# TOP.net
KiCad netlist of a schematic drawn in Altium Designer
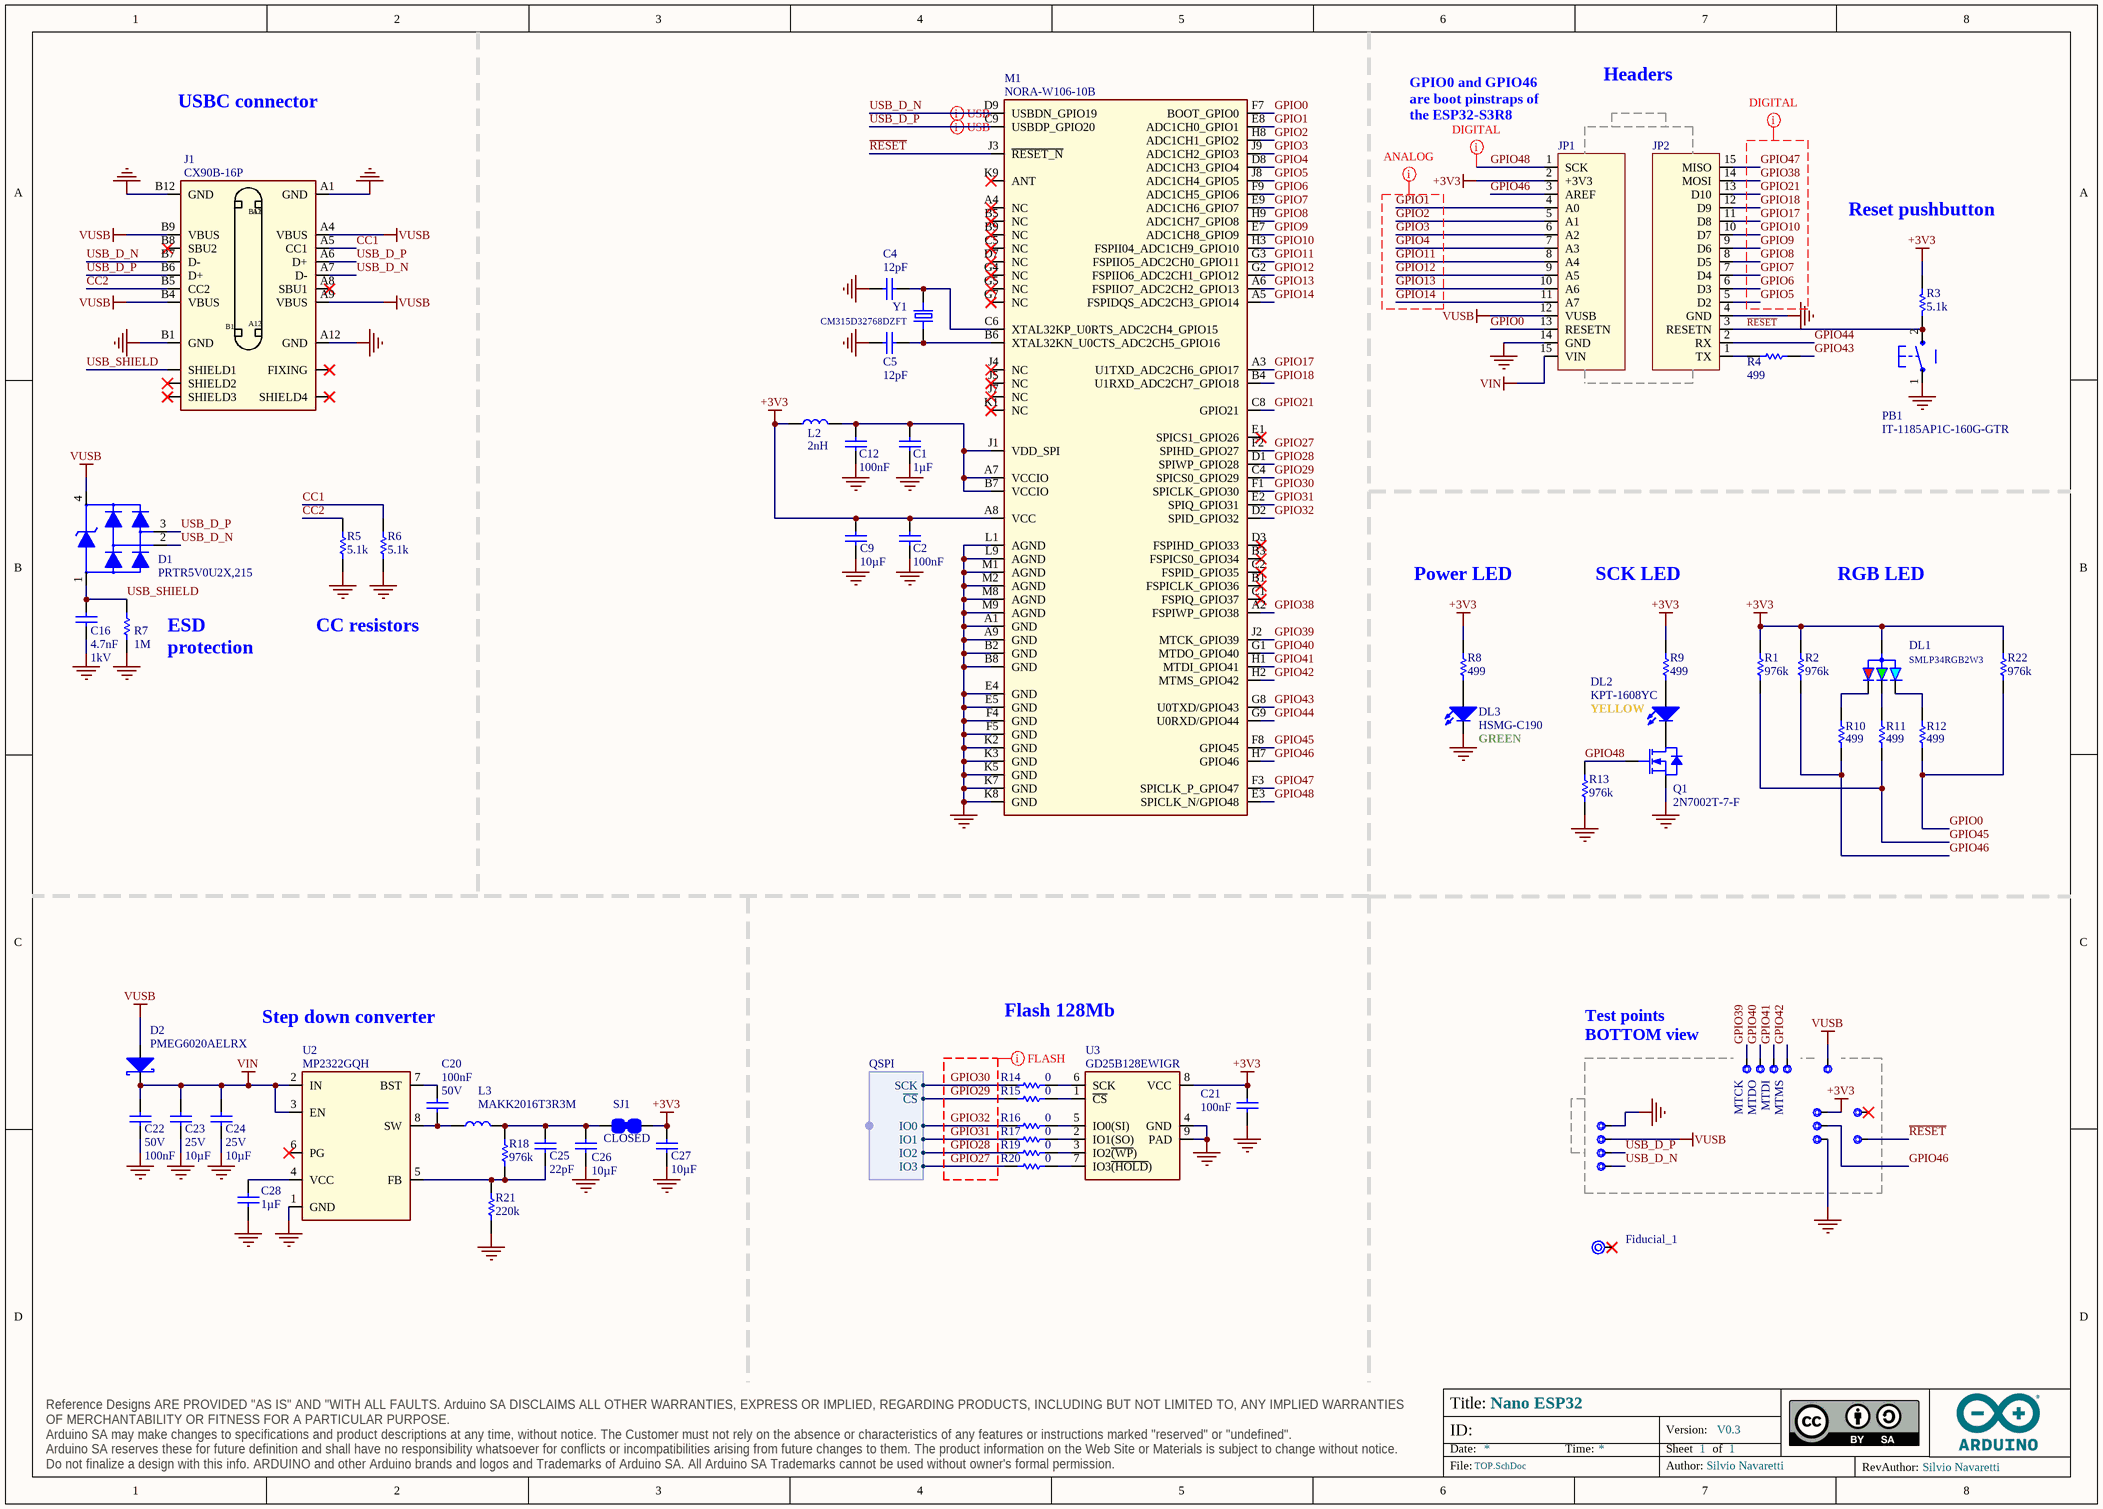
[diagram p0: TOP.SchDoc]

(export (version "E")
  (design (tool "Eeschema 10.0.6"))
  (components
    (comp (ref "3V3")
      (value "CMP-018-0005-A.3")
      (footprint "TP-1.00MM")
      (description "Test point 1.00mm")
      (libsource (lib "Clean") (part "TESTPOINT"))
    )
    (comp (ref "C1")
      (value "1µF")
      (footprint "CAP-0201")
      (description "CAP CHIP 0201 1uF 6.3V X5R 20%")
      (fields (field (name "VOLTAGE") "6.3V") (field (name "PART NUMBER") "GRM033R60J105MEA2D"))
      (libsource (lib "Clean") (part "CAP"))
    )
    (comp (ref "C2")
      (value "100nF")
      (footprint "CAP-0402")
      (description "CAP CHIP 0402 100nF 50V X5R 10%")
      (fields (field (name "VOLTAGE") "50V") (field (name "PART NUMBER") "GRM155R61H104KE19D"))
      (libsource (lib "Clean") (part "CAP"))
    )
    (comp (ref "C4")
      (value "12pF")
      (footprint "CAP-0201")
      (description "CAP CHIP 0201 12pF 25V C0G 5%")
      (fields (field (name "PART NUMBER") "GRM0335C1E120JA01J") (field (name "MANUFACTURER") "Murata"))
      (libsource (lib "Clean") (part "CAP"))
    )
    (comp (ref "C5")
      (value "12pF")
      (footprint "CAP-0201")
      (description "CAP CHIP 0201 12pF 25V C0G 5%")
      (fields (field (name "PART NUMBER") "GRM0335C1E120JA01J") (field (name "MANUFACTURER") "Murata"))
      (libsource (lib "Clean") (part "CAP"))
    )
    (comp (ref "C9")
      (value "10µF")
      (footprint "CAP-0603")
      (description "CAP CHIP 0603 10uF 25V X5R 20%")
      (fields (field (name "VOLTAGE") "25V") (field (name "PART NUMBER") "GRM188R61E106MA73J"))
      (libsource (lib "Clean") (part "CAP"))
    )
    (comp (ref "C12")
      (value "100nF")
      (footprint "CAP-0402")
      (description "CAP CHIP 0402 100nF 50V X5R 10%")
      (fields (field (name "VOLTAGE") "50V") (field (name "PART NUMBER") "GRM155R61H104KE19D"))
      (libsource (lib "Clean") (part "CAP"))
    )
    (comp (ref "C16")
      (value "4.7nF")
      (footprint "CAP-0805")
      (description "CAP CHIP 0805 4.7nF 1000V X7R 10%")
      (fields
        (field (name "MANUFACTURER") "KEMET")
        (field (name "VOLTAGE") "1kV")
        (field (name "TOLERANCE") "10%")
      )
      (libsource (lib "Clean") (part "CAP"))
    )
    (comp (ref "C20")
      (value "100nF")
      (footprint "CAP-0402")
      (description "CAP CHIP 0402 100nF 50V X5R 10%")
      (fields
        (field (name "VOLTAGE") "50V")
        (field (name "PART NUMBER") "GRM155R61H104KE19D")
        (field (name "MANUFACTURER") "Murata")
      )
      (libsource (lib "Clean") (part "CAP"))
    )
    (comp (ref "C21")
      (value "100nF")
      (footprint "CAP-0402")
      (description "CAP CHIP 0402 100nF 50V X5R 10%")
      (fields (field (name "VOLTAGE") "50V") (field (name "PART NUMBER") "GRM155R61H104KE19D"))
      (libsource (lib "Clean") (part "CAP"))
    )
    (comp (ref "C22")
      (value "100nF")
      (footprint "CAP-0402")
      (description "CAP CHIP 0402 100nF 50V X5R 10%")
      (fields
        (field (name "MANUFACTURER") "Murata")
        (field (name "PART NUMBER") "GRM155R61H104KE19D")
        (field (name "VOLTAGE") "50V")
      )
      (libsource (lib "Clean") (part "CAP"))
    )
    (comp (ref "C23")
      (value "10µF")
      (footprint "CAP-0603")
      (description "CAP CHIP 0603 10uF 25V X5R 20%")
      (fields
        (field (name "VOLTAGE") "25V")
        (field (name "PART NUMBER") "GRM188R61E106MA73J")
        (field (name "TOLERANCE") "20%")
      )
      (libsource (lib "Clean") (part "CAP"))
    )
    (comp (ref "C24")
      (value "10µF")
      (footprint "CAP-0603")
      (description "CAP CHIP 0603 10uF 25V X5R 20%")
      (fields
        (field (name "VOLTAGE") "25V")
        (field (name "PART NUMBER") "GRM188R61E106MA73J")
        (field (name "TOLERANCE") "20%")
      )
      (libsource (lib "Clean") (part "CAP"))
    )
    (comp (ref "C25")
      (value "22pF")
      (footprint "CAP-0402")
      (description "CAP CHIP 0402 22pF 50V C0G 5%")
      (fields (field (name "TOLERANCE") "5%") (field (name "PART NUMBER") "C0402C220J5GAC7411"))
      (libsource (lib "Clean") (part "CAP"))
    )
    (comp (ref "C26")
      (value "10µF")
      (footprint "CAP-0603")
      (description "CAP CHIP 0603 10uF 25V X5R 20%")
      (fields (field (name "VOLTAGE") "25V") (field (name "PART NUMBER") "GRM188R61E106MA73J"))
      (libsource (lib "Clean") (part "CAP"))
    )
    (comp (ref "C27")
      (value "10µF")
      (footprint "CAP-0603")
      (description "CAP CHIP 0603 10uF 25V X5R 20%")
      (fields (field (name "VOLTAGE") "25V") (field (name "PART NUMBER") "GRM188R61E106MA73J"))
      (libsource (lib "Clean") (part "CAP"))
    )
    (comp (ref "C28")
      (value "1µF")
      (footprint "CAP-0201")
      (description "CAP CHIP 0201 1uF 6.3V X5R 20%")
      (fields (field (name "TOLERANCE") "20%") (field (name "MANUFACTURER") "Murata"))
      (libsource (lib "Clean") (part "CAP"))
    )
    (comp (ref "D+1")
      (value "CMP-018-0005-A.3")
      (footprint "TP-1.00MM")
      (description "Test point 1.00mm")
      (libsource (lib "Clean") (part "TESTPOINT"))
    )
    (comp (ref "D-1")
      (value "CMP-018-0005-A.3")
      (footprint "TP-1.00MM")
      (description "Test point 1.00mm")
      (libsource (lib "Clean") (part "TESTPOINT"))
    )
    (comp (ref "D1")
      (value "PRTR5V0U2X,215")
      (footprint "SOT190P230X110-4N")
      (description "TVS ARRAY 4LIN.8kV 1pF SOT143B")
      (fields (field (name "MANUFACTURER") "Nexperia"))
      (libsource (lib "Clean") (part "PRTR5V0U2X,215"))
    )
    (comp (ref "D2")
      (value "PMEG6020AELRX")
      (footprint "SOD123-1")
      (description "DIODE SCHOTTKY SMD 2A 60V SOD123FL")
      (fields (field (name "MANUFACTURER") "Nexperia"))
      (libsource (lib "Clean") (part "PMEG6020AELRX"))
    )
    (comp (ref "DL1")
      (value "SMLP34RGB2W3")
      (footprint "SMLP34RGB2W")
      (description "LED RGB DIFFUSED PICOLED SMD")
      (fields (field (name "MANUFACTURER") "ROHM Semiconductor"))
      (libsource (lib "Clean") (part "SMLP34RGB2W3"))
    )
    (comp (ref "DL2")
      (value "KPT-1608YC")
      (footprint "LEDC1608X80N-AK")
      (description "LED SMD 0603 GIA588   8mcd 120^")
      (fields (field (name "MANUFACTURER") "Kingbright"))
      (libsource (lib "Clean") (part "LED"))
    )
    (comp (ref "DL3")
      (value "HSMG-C190")
      (footprint "LEDC1608X80N-AK")
      (description "LED SMD 0603 GREEN/568 15mcd 120^")
      (fields (field (name "MANUFACTURER") "Broadcom"))
      (libsource (lib "Clean") (part "LED"))
    )
    (comp (ref "Fiducial_1")
      (value "Fiducial mark 1mm with 2mm solder")
      (footprint "Fiducial mark 1mm with circle-Footprint-1")
      (libsource (lib "Clean") (part "Fiducial mark 1mm with circle"))
    )
    (comp (ref "GND1")
      (value "CMP-018-0005-A.3")
      (footprint "TP-1.00MM")
      (description "Test point 1.00mm")
      (libsource (lib "Clean") (part "TESTPOINT"))
    )
    (comp (ref "GND2")
      (value "CMP-018-0005-A.3")
      (footprint "TP-1.00MM")
      (description "Test point 1.00mm")
      (libsource (lib "Clean") (part "TESTPOINT"))
    )
    (comp (ref "GPIO46")
      (value "CMP-018-0005-A.3")
      (footprint "TP-1.00MM")
      (description "Test point 1.00mm")
      (libsource (lib "Clean") (part "TESTPOINT"))
    )
    (comp (ref "J1")
      (value "CX90B-16P")
      (footprint "CX90B-16P-Footprint-1")
      (description "CONN RCPT USB3.1 TYPEC 16POS SMD")
      (fields (field (name "MANUFACTURER") "Hirose"))
      (libsource (lib "Clean") (part "CX90B-16P-Symbol-1"))
    )
    (comp (ref "JP1")
      (value "PINHD-1X15-NANO-ANALOG-CASTELLATED")
      (footprint "PINHD-1X14_5VF")
      (description "CONN THD SOCKET F/1/D 15V JANALOG NANO-TYPE CASTELLATED")
      (libsource (lib "Clean") (part "PINHD-1X15-NANO-ANALOG-CASTELLATED"))
    )
    (comp (ref "JP2")
      (value "PINHD-1X15-NANO-DIGITAL-CASTELLATED")
      (footprint "PINHD-1X14_5VF")
      (description "CONN THD SOCKET F/1/D 15V JDIGITAL NANO-TYPE CASTELLATED")
      (libsource (lib "Clean") (part "J0183-A.1"))
    )
    (comp (ref "L2")
      (value "BSCH001005052N0SCP")
      (footprint "L-0402")
      (description "IND CHIP 0402 2nH +-0.3nH 400mA")
      (fields (field (name "MANUFACTURER") "Pulse Electronics") (field (name "INDUCTANCE") "2nH"))
      (libsource (lib "Clean") (part "Inductor"))
    )
    (comp (ref "L3")
      (value "MAKK2016T3R3M")
      (footprint "MAKK2016T3R3M-Footprint-1")
      (description "IND CHIP 0806 3.3 uH 20% 1.2A")
      (fields (field (name "TOLERANCE") "20%") (field (name "MANUFACTURER") "Taiyo Yuden"))
      (libsource (lib "Clean") (part "Inductor"))
    )
    (comp (ref "M1")
      (value "NORA-W106-10B")
      (footprint "NORA-W106-Footprint-1")
      (description "MODULE WIFI +BLE5 ESP32-S3")
      (fields (field (name "MANUFACTURER") "U-Blox"))
      (libsource (lib "Clean") (part "NORA-W106-10B"))
    )
    (comp (ref "MTCK")
      (value "CMP-018-0005-A.3")
      (footprint "TP-1.00MM")
      (description "Test point 1.00mm")
      (libsource (lib "Clean") (part "TESTPOINT"))
    )
    (comp (ref "MTDI")
      (value "CMP-018-0005-A.3")
      (footprint "TP-1.00MM")
      (description "Test point 1.00mm")
      (libsource (lib "Clean") (part "TESTPOINT"))
    )
    (comp (ref "MTDO")
      (value "CMP-018-0005-A.3")
      (footprint "TP-1.00MM")
      (description "Test point 1.00mm")
      (libsource (lib "Clean") (part "TESTPOINT"))
    )
    (comp (ref "MTMS")
      (value "CMP-018-0005-A.3")
      (footprint "TP-1.00MM")
      (description "Test point 1.00mm")
      (libsource (lib "Clean") (part "TESTPOINT"))
    )
    (comp (ref "NC1")
      (value "CMP-018-0005-A.3")
      (footprint "TP-1.00MM")
      (description "Test point 1.00mm")
      (libsource (lib "Clean") (part "TESTPOINT"))
    )
    (comp (ref "NC2")
      (value "CMP-018-0005-A.3")
      (footprint "TP-1.00MM")
      (description "Test point 1.00mm")
      (libsource (lib "Clean") (part "TESTPOINT"))
    )
    (comp (ref "PB1")
      (value "IT-1185AP1C-160G-GTR")
      (footprint "C&K_PTS820_NO_HOLES-1")
      (description "PUSHBUTTON WHITE NO ANCHORS")
      (fields (field (name "MANUFACTURER") "Switronic"))
      (libsource (lib "Clean") (part "PTS820"))
    )
    (comp (ref "Q1")
      (value "2N7002T-7-F")
      (footprint "SOT523")
      (description "MOSFET N-CH 60V 115mA SOT523")
      (fields (field (name "MANUFACTURER") "Diodes Inc."))
      (libsource (lib "Clean") (part "NMOS"))
    )
    (comp (ref "R1")
      (value "976k")
      (footprint "RES-0201")
      (description "RES CHIP 0201 976k 1/20W 1%")
      (fields (field (name "TOLERANCE") "1%") (field (name "POWER") "50mW"))
      (libsource (lib "Clean") (part "RES"))
    )
    (comp (ref "R2")
      (value "976k")
      (footprint "RES-0201")
      (description "RES CHIP 0201 976k 1/20W 1%")
      (fields (field (name "TOLERANCE") "1%") (field (name "POWER") "50mW"))
      (libsource (lib "Clean") (part "RES"))
    )
    (comp (ref "R3")
      (value "5.1k")
      (footprint "RES-0201")
      (description "RES CHIP 0201 5.1k OHM 1/20W 1%")
      (fields (field (name "PART NUMBER") "RC0201FR-075K1L") (field (name "MANUFACTURER") "Yageo"))
      (libsource (lib "Clean") (part "RES"))
    )
    (comp (ref "R4")
      (value "499")
      (footprint "RES-0201")
      (description "RES CHIP 0201 499R 1/20W 1%")
      (fields (field (name "POWER") "50mW") (field (name "MANUFACTURER") "Vishay"))
      (libsource (lib "Clean") (part "RES"))
    )
    (comp (ref "R5")
      (value "5.1k")
      (footprint "RES-0201")
      (description "RES CHIP 0201 5.1k OHM 1/20W 1%")
      (fields (field (name "POWER") "50mW") (field (name "MANUFACTURER") "Yageo"))
      (libsource (lib "Clean") (part "RES"))
    )
    (comp (ref "R6")
      (value "5.1k")
      (footprint "RES-0201")
      (description "RES CHIP 0201 5.1k OHM 1/20W 1%")
      (fields (field (name "POWER") "50mW") (field (name "MANUFACTURER") "Yageo"))
      (libsource (lib "Clean") (part "RES"))
    )
    (comp (ref "R7")
      (value "1M")
      (footprint "RES-0402")
      (description "RES CHIP 0402 1M 1% 1/16W")
      (fields (field (name "MANUFACTURER") "Vishay") (field (name "POWER") "63mW"))
      (libsource (lib "Clean") (part "RES"))
    )
    (comp (ref "R8")
      (value "499")
      (footprint "RES-0201")
      (description "RES CHIP 0201 499R 1/20W 1%")
      (fields (field (name "PART NUMBER") "CRCW0201499RFKED") (field (name "TOLERANCE") "1%"))
      (libsource (lib "Clean") (part "RES"))
    )
    (comp (ref "R9")
      (value "499")
      (footprint "RES-0201")
      (description "RES CHIP 0201 499R 1/20W 1%")
      (fields (field (name "PART NUMBER") "CRCW0201499RFKED") (field (name "TOLERANCE") "1%"))
      (libsource (lib "Clean") (part "RES"))
    )
    (comp (ref "R10")
      (value "499")
      (footprint "RES-0201")
      (description "RES CHIP 0201 499R 1/20W 1%")
      (fields (field (name "MANUFACTURER") "Vishay") (field (name "POWER") "50mW"))
      (libsource (lib "Clean") (part "RES"))
    )
    (comp (ref "R11")
      (value "499")
      (footprint "RES-0201")
      (description "RES CHIP 0201 499R 1/20W 1%")
      (fields (field (name "MANUFACTURER") "Vishay") (field (name "POWER") "50mW"))
      (libsource (lib "Clean") (part "RES"))
    )
    (comp (ref "R12")
      (value "499")
      (footprint "RES-0201")
      (description "RES CHIP 0201 499R 1/20W 1%")
      (fields (field (name "MANUFACTURER") "Vishay") (field (name "POWER") "50mW"))
      (libsource (lib "Clean") (part "RES"))
    )
    (comp (ref "R13")
      (value "976k")
      (footprint "RES-0201")
      (description "RES CHIP 0201 976k 1/20W 1%")
      (fields (field (name "TOLERANCE") "1%") (field (name "POWER") "50mW"))
      (libsource (lib "Clean") (part "RES"))
    )
    (comp (ref "R14")
      (value "0")
      (footprint "RES-0201")
      (description "RES CHIP 0201 0R 1/20W 5%")
      (fields (field (name "POWER") "50mW") (field (name "TOLERANCE") "5%"))
      (libsource (lib "Clean") (part "RES"))
    )
    (comp (ref "R15")
      (value "0")
      (footprint "RES-0201")
      (description "RES CHIP 0201 0R 1/20W 5%")
      (fields (field (name "POWER") "50mW") (field (name "TOLERANCE") "5%"))
      (libsource (lib "Clean") (part "RES"))
    )
    (comp (ref "R16")
      (value "0")
      (footprint "RES-0201")
      (description "RES CHIP 0201 0R 1/20W 5%")
      (fields (field (name "POWER") "50mW") (field (name "TOLERANCE") "5%"))
      (libsource (lib "Clean") (part "RES"))
    )
    (comp (ref "R17")
      (value "0")
      (footprint "RES-0201")
      (description "RES CHIP 0201 0R 1/20W 5%")
      (fields (field (name "POWER") "50mW") (field (name "TOLERANCE") "5%"))
      (libsource (lib "Clean") (part "RES"))
    )
    (comp (ref "R18")
      (value "976k")
      (footprint "RES-0201")
      (description "RES CHIP 0201 976k 1/20W 1%")
      (fields (field (name "TOLERANCE") "1%") (field (name "POWER") "50mW"))
      (libsource (lib "Clean") (part "RES"))
    )
    (comp (ref "R19")
      (value "0")
      (footprint "RES-0201")
      (description "RES CHIP 0201 0R 1/20W 5%")
      (fields (field (name "POWER") "50mW") (field (name "TOLERANCE") "5%"))
      (libsource (lib "Clean") (part "RES"))
    )
    (comp (ref "R20")
      (value "0")
      (footprint "RES-0201")
      (description "RES CHIP 0201 0R 1/20W 5%")
      (fields (field (name "POWER") "50mW") (field (name "TOLERANCE") "5%"))
      (libsource (lib "Clean") (part "RES"))
    )
    (comp (ref "R21")
      (value "220k")
      (footprint "RES-0201")
      (description "RES CHIP 0201 220k 1% 1/20W")
      (fields (field (name "MANUFACTURER") "Yageo") (field (name "PART NUMBER") "AC0201FR-07220KL"))
      (libsource (lib "Clean") (part "RES"))
    )
    (comp (ref "R22")
      (value "976k")
      (footprint "RES-0201")
      (description "RES CHIP 0201 976k 1/20W 1%")
      (fields (field (name "TOLERANCE") "1%") (field (name "POWER") "50mW"))
      (libsource (lib "Clean") (part "RES"))
    )
    (comp (ref "SJ1")
      (value "SMD solder JUMPER CLOSED")
      (footprint "SJ")
      (description "Solder Jumper shorted pads. This is not a component")
      (libsource (lib "Clean") (part "CLOSED"))
    )
    (comp (ref "TP_VUSB")
      (value "CMP-018-0005-A.3")
      (footprint "TP-1.00MM")
      (description "Test point 1.00mm")
      (libsource (lib "Clean") (part "TESTPOINT"))
    )
    (comp (ref "U2")
      (value "MP2322GQH")
      (footprint "QFN50P150X200X90-8L")
      (description "IC STEP DOWN CONV 1A 22V QFN8")
      (fields (field (name "MANUFACTURER") "Monolithic Power Systems"))
      (libsource (lib "Clean") (part "MP2322GQH"))
    )
    (comp (ref "U3")
      (value "GD25B128EWIGR")
      (footprint "PSON127P600X60_HS-9N")
      (description "IC FLASH 128MB 6DFN 3V")
      (fields (field (name "MANUFACTURER") "Giga Devices"))
      (libsource (lib "Clean") (part "GD25B128EWIGR"))
    )
    (comp (ref "VUSB")
      (value "CMP-018-0005-A.3")
      (footprint "TP-1.00MM")
      (description "Test point 1.00mm")
      (libsource (lib "Clean") (part "TESTPOINT"))
    )
    (comp (ref "Y1")
      (value "CM315D32768DZFT")
      (footprint "ABS07")
      (description "CRYSTAL 32.768kHz 20ppm 12.5pF SMD 1.6x0.9mm")
      (fields (field (name "MANUFACTURER") "Citizen FineDevice"))
      (libsource (lib "Clean") (part "Crystal"))
    )
  )
  (nets
    (net (code "1") (name "+3V3") (class "Default")
      (node (ref "3V3") (pin "X") (pinfunction "X_X") (pintype "passive"))
      (node (ref "C2") (pin "2") (pinfunction "2_2") (pintype "passive"))
      (node (ref "C21") (pin "2") (pinfunction "2_2") (pintype "passive"))
      (node (ref "C27") (pin "2") (pinfunction "2_2") (pintype "passive"))
      (node (ref "C9") (pin "2") (pinfunction "2_2") (pintype "passive"))
      (node (ref "DL1") (pin "1") (pinfunction "ANODE_1") (pintype "passive"))
      (node (ref "JP1") (pin "2") (pinfunction "+3V3_2") (pintype "passive"))
      (node (ref "L2") (pin "1") (pinfunction "1_1") (pintype "passive"))
      (node (ref "M1") (pin "A8") (pinfunction "VCC_A8") (pintype "power_in"))
      (node (ref "R1") (pin "2") (pinfunction "2_2") (pintype "passive"))
      (node (ref "R2") (pin "2") (pinfunction "2_2") (pintype "passive"))
      (node (ref "R22") (pin "2") (pinfunction "2_2") (pintype "passive"))
      (node (ref "R3") (pin "2") (pinfunction "2_2") (pintype "passive"))
      (node (ref "R8") (pin "2") (pinfunction "2_2") (pintype "passive"))
      (node (ref "R9") (pin "2") (pinfunction "2_2") (pintype "passive"))
      (node (ref "SJ1") (pin "2") (pinfunction "2_2") (pintype "passive"))
      (node (ref "U3") (pin "8") (pinfunction "VCC_8") (pintype "passive"))
    )
    (net (code "2") (name "/CC1") (class "Default")
      (node (ref "J1") (pin "A5") (pinfunction "CC1_A5") (pintype "passive"))
      (node (ref "R6") (pin "2") (pinfunction "2_2") (pintype "passive"))
    )
    (net (code "3") (name "/CC2") (class "Default")
      (node (ref "J1") (pin "B5") (pinfunction "CC2_B5") (pintype "passive"))
      (node (ref "R5") (pin "2") (pinfunction "2_2") (pintype "passive"))
    )
    (net (code "4") (name "/GPIO0") (class "Default")
      (node (ref "JP1") (pin "13") (pinfunction "RESETN_13") (pintype "passive"))
      (node (ref "M1") (pin "F7") (pinfunction "BOOT_GPIO0_F7") (pintype "passive"))
      (node (ref "R12") (pin "1") (pinfunction "1_1") (pintype "passive"))
      (node (ref "R22") (pin "1") (pinfunction "1_1") (pintype "passive"))
    )
    (net (code "5") (name "/GPIO1") (class "Default")
      (node (ref "JP1") (pin "4") (pinfunction "A0_4") (pintype "passive"))
      (node (ref "M1") (pin "E8") (pinfunction "ADC1CH0_GPIO1_E8") (pintype "passive"))
    )
    (net (code "6") (name "/GPIO2") (class "Default")
      (node (ref "JP1") (pin "5") (pinfunction "A1_5") (pintype "passive"))
      (node (ref "M1") (pin "H8") (pinfunction "ADC1CH1_GPIO2_H8") (pintype "passive"))
    )
    (net (code "7") (name "/GPIO3") (class "Default")
      (node (ref "JP1") (pin "6") (pinfunction "A2_6") (pintype "passive"))
      (node (ref "M1") (pin "J9") (pinfunction "ADC1CH2_GPIO3_J9") (pintype "passive"))
    )
    (net (code "8") (name "/GPIO4") (class "Default")
      (node (ref "JP1") (pin "7") (pinfunction "A3_7") (pintype "passive"))
      (node (ref "M1") (pin "D8") (pinfunction "ADC1CH3_GPIO4_D8") (pintype "passive"))
    )
    (net (code "9") (name "/GPIO5") (class "Default")
      (node (ref "JP2") (pin "5") (pinfunction "D2_5") (pintype "passive"))
      (node (ref "M1") (pin "J8") (pinfunction "ADC1CH4_GPIO5_J8") (pintype "passive"))
    )
    (net (code "10") (name "/GPIO6") (class "Default")
      (node (ref "JP2") (pin "6") (pinfunction "D3_6") (pintype "passive"))
      (node (ref "M1") (pin "F9") (pinfunction "ADC1CH5_GPIO6_F9") (pintype "passive"))
    )
    (net (code "11") (name "/GPIO7") (class "Default")
      (node (ref "JP2") (pin "7") (pinfunction "D4_7") (pintype "passive"))
      (node (ref "M1") (pin "E9") (pinfunction "ADC1CH6_GPIO7_E9") (pintype "passive"))
    )
    (net (code "12") (name "/GPIO8") (class "Default")
      (node (ref "JP2") (pin "8") (pinfunction "D5_8") (pintype "passive"))
      (node (ref "M1") (pin "H9") (pinfunction "ADC1CH7_GPIO8_H9") (pintype "passive"))
    )
    (net (code "13") (name "/GPIO9") (class "Default")
      (node (ref "JP2") (pin "9") (pinfunction "D6_9") (pintype "passive"))
      (node (ref "M1") (pin "E7") (pinfunction "ADC1CH8_GPIO9_E7") (pintype "passive"))
    )
    (net (code "14") (name "/GPIO10") (class "Default")
      (node (ref "JP2") (pin "10") (pinfunction "D7_10") (pintype "passive"))
      (node (ref "M1") (pin "H3") (pinfunction "FSPII04_ADC1CH9_GPIO10_H3") (pintype "passive"))
    )
    (net (code "15") (name "/GPIO11") (class "Default")
      (node (ref "JP1") (pin "8") (pinfunction "A4_8") (pintype "passive"))
      (node (ref "M1") (pin "G3") (pinfunction "FSPIIO5_ADC2CH0_GPIO11_G3") (pintype "passive"))
    )
    (net (code "16") (name "/GPIO12") (class "Default")
      (node (ref "JP1") (pin "9") (pinfunction "A5_9") (pintype "passive"))
      (node (ref "M1") (pin "G2") (pinfunction "FSPIIO6_ADC2CH1_GPIO12_G2") (pintype "passive"))
    )
    (net (code "17") (name "/GPIO13") (class "Default")
      (node (ref "JP1") (pin "10") (pinfunction "A6_10") (pintype "passive"))
      (node (ref "M1") (pin "A6") (pinfunction "FSPIIO7_ADC2CH2_GPIO13_A6") (pintype "passive"))
    )
    (net (code "18") (name "/GPIO14") (class "Default")
      (node (ref "JP1") (pin "11") (pinfunction "A7_11") (pintype "passive"))
      (node (ref "M1") (pin "A5") (pinfunction "FSPIDQS_ADC2CH3_GPIO14_A5") (pintype "passive"))
    )
    (net (code "19") (name "/GPIO17") (class "Default")
      (node (ref "JP2") (pin "11") (pinfunction "D8_11") (pintype "passive"))
      (node (ref "M1") (pin "A3") (pinfunction "U1TXD_ADC2CH6_GPIO17_A3") (pintype "passive"))
    )
    (net (code "20") (name "/GPIO18") (class "Default")
      (node (ref "JP2") (pin "12") (pinfunction "D9_12") (pintype "passive"))
      (node (ref "M1") (pin "B4") (pinfunction "U1RXD_ADC2CH7_GPIO18_B4") (pintype "passive"))
    )
    (net (code "21") (name "/GPIO21") (class "Default")
      (node (ref "JP2") (pin "13") (pinfunction "D10_13") (pintype "passive"))
      (node (ref "M1") (pin "C8") (pinfunction "GPIO21_C8") (pintype "passive"))
    )
    (net (code "22") (name "/GPIO27") (class "Default")
      (node (ref "M1") (pin "F2") (pinfunction "SPIHD_GPIO27_F2") (pintype "passive"))
      (node (ref "R20") (pin "1") (pinfunction "1_1") (pintype "passive"))
    )
    (net (code "23") (name "/GPIO28") (class "Default")
      (node (ref "M1") (pin "D1") (pinfunction "SPIWP_GPIO28_D1") (pintype "passive"))
      (node (ref "R19") (pin "1") (pinfunction "1_1") (pintype "passive"))
    )
    (net (code "24") (name "/GPIO29") (class "Default")
      (node (ref "M1") (pin "C4") (pinfunction "SPICS0_GPIO29_C4") (pintype "passive"))
      (node (ref "R15") (pin "1") (pinfunction "1_1") (pintype "passive"))
    )
    (net (code "25") (name "/GPIO30") (class "Default")
      (node (ref "M1") (pin "F1") (pinfunction "SPICLK_GPIO30_F1") (pintype "passive"))
      (node (ref "R14") (pin "1") (pinfunction "1_1") (pintype "passive"))
    )
    (net (code "26") (name "/GPIO31") (class "Default")
      (node (ref "M1") (pin "E2") (pinfunction "SPIQ_GPIO31_E2") (pintype "passive"))
      (node (ref "R17") (pin "1") (pinfunction "1_1") (pintype "passive"))
    )
    (net (code "27") (name "/GPIO32") (class "Default")
      (node (ref "M1") (pin "D2") (pinfunction "SPID_GPIO32_D2") (pintype "passive"))
      (node (ref "R16") (pin "1") (pinfunction "1_1") (pintype "passive"))
    )
    (net (code "28") (name "/GPIO38") (class "Default")
      (node (ref "JP2") (pin "14") (pinfunction "MOSI_14") (pintype "passive"))
      (node (ref "M1") (pin "A2") (pinfunction "FSPIWP_GPIO38_A2") (pintype "passive"))
    )
    (net (code "29") (name "/GPIO39") (class "Default")
      (node (ref "M1") (pin "J2") (pinfunction "MTCK_GPIO39_J2") (pintype "passive"))
      (node (ref "MTCK") (pin "X") (pinfunction "X_X") (pintype "passive"))
    )
    (net (code "30") (name "/GPIO40") (class "Default")
      (node (ref "M1") (pin "G1") (pinfunction "MTDO_GPIO40_G1") (pintype "passive"))
      (node (ref "MTDO") (pin "X") (pinfunction "X_X") (pintype "passive"))
    )
    (net (code "31") (name "/GPIO41") (class "Default")
      (node (ref "M1") (pin "H1") (pinfunction "MTDI_GPIO41_H1") (pintype "passive"))
      (node (ref "MTDI") (pin "X") (pinfunction "X_X") (pintype "passive"))
    )
    (net (code "32") (name "/GPIO42") (class "Default")
      (node (ref "M1") (pin "H2") (pinfunction "MTMS_GPIO42_H2") (pintype "passive"))
      (node (ref "MTMS") (pin "X") (pinfunction "X_X") (pintype "passive"))
    )
    (net (code "33") (name "/GPIO43") (class "Default")
      (node (ref "M1") (pin "G8") (pinfunction "U0TXD/GPIO43_G8") (pintype "passive"))
      (node (ref "R4") (pin "2") (pinfunction "2_2") (pintype "passive"))
    )
    (net (code "34") (name "/GPIO44") (class "Default")
      (node (ref "JP2") (pin "2") (pinfunction "RX_2") (pintype "passive"))
      (node (ref "M1") (pin "G9") (pinfunction "U0RXD/GPIO44_G9") (pintype "passive"))
    )
    (net (code "35") (name "/GPIO45") (class "Default")
      (node (ref "M1") (pin "F8") (pinfunction "GPIO45_F8") (pintype "passive"))
      (node (ref "R1") (pin "1") (pinfunction "1_1") (pintype "passive"))
      (node (ref "R11") (pin "1") (pinfunction "1_1") (pintype "passive"))
    )
    (net (code "36") (name "/GPIO46") (class "Default")
      (node (ref "GPIO46") (pin "X") (pinfunction "X_X") (pintype "passive"))
      (node (ref "JP1") (pin "3") (pinfunction "AREF_3") (pintype "passive"))
      (node (ref "M1") (pin "H7") (pinfunction "GPIO46_H7") (pintype "passive"))
      (node (ref "R10") (pin "1") (pinfunction "1_1") (pintype "passive"))
      (node (ref "R2") (pin "1") (pinfunction "1_1") (pintype "passive"))
    )
    (net (code "37") (name "/GPIO47") (class "Default")
      (node (ref "JP2") (pin "15") (pinfunction "MISO_15") (pintype "passive"))
      (node (ref "M1") (pin "F3") (pinfunction "SPICLK_P_GPIO47_F3") (pintype "passive"))
    )
    (net (code "38") (name "/GPIO48") (class "Default")
      (node (ref "JP1") (pin "1") (pinfunction "SCK_1") (pintype "passive"))
      (node (ref "M1") (pin "E3") (pinfunction "SPICLK_N/GPIO48_E3") (pintype "passive"))
      (node (ref "Q1") (pin "G") (pinfunction "G_G") (pintype "passive"))
      (node (ref "R13") (pin "2") (pinfunction "2_2") (pintype "passive"))
    )
    (net (code "39") (name "/USB_D_N") (class "Default")
      (node (ref "D-1") (pin "X") (pinfunction "X_X") (pintype "passive"))
      (node (ref "D1") (pin "2") (pinfunction "2_2") (pintype "passive"))
      (node (ref "J1") (pin "A7") (pinfunction "D-_A7") (pintype "passive"))
      (node (ref "J1") (pin "B7") (pinfunction "D-_B7") (pintype "passive"))
      (node (ref "M1") (pin "D9") (pinfunction "USBDN_GPIO19_D9") (pintype "passive"))
    )
    (net (code "40") (name "/USB_D_P") (class "Default")
      (node (ref "D+1") (pin "X") (pinfunction "X_X") (pintype "passive"))
      (node (ref "D1") (pin "3") (pinfunction "3_3") (pintype "passive"))
      (node (ref "J1") (pin "A6") (pinfunction "D+_A6") (pintype "passive"))
      (node (ref "J1") (pin "B6") (pinfunction "D+_B6") (pintype "passive"))
      (node (ref "M1") (pin "C9") (pinfunction "USBDP_GPIO20_C9") (pintype "passive"))
    )
    (net (code "41") (name "/USB_SHIELD") (class "Default")
      (node (ref "C16") (pin "2") (pinfunction "2_2") (pintype "passive"))
      (node (ref "D1") (pin "1") (pinfunction "1_1") (pintype "passive"))
      (node (ref "J1") (pin "SHIELD1") (pinfunction "SHIELD1_SHIELD1") (pintype "passive"))
      (node (ref "R7") (pin "2") (pinfunction "2_2") (pintype "passive"))
    )
    (net (code "42") (name "/~{RESET}") (class "Default")
      (node (ref "JP2") (pin "3") (pinfunction "RESETN_3") (pintype "passive"))
      (node (ref "M1") (pin "J3") (pinfunction "~{RESET_N}_J3") (pintype "passive"))
      (node (ref "NC2") (pin "X") (pinfunction "X_X") (pintype "passive"))
      (node (ref "PB1") (pin "2") (pinfunction "2_2") (pintype "passive"))
      (node (ref "R3") (pin "1") (pinfunction "1_1") (pintype "passive"))
    )
    (net (code "43") (name "GND") (class "Default")
      (node (ref "C1") (pin "1") (pinfunction "1_1") (pintype "passive"))
      (node (ref "C12") (pin "1") (pinfunction "1_1") (pintype "passive"))
      (node (ref "C16") (pin "1") (pinfunction "1_1") (pintype "passive"))
      (node (ref "C2") (pin "1") (pinfunction "1_1") (pintype "passive"))
      (node (ref "C21") (pin "1") (pinfunction "1_1") (pintype "passive"))
      (node (ref "C22") (pin "2") (pinfunction "2_2") (pintype "passive"))
      (node (ref "C23") (pin "1") (pinfunction "1_1") (pintype "passive"))
      (node (ref "C24") (pin "1") (pinfunction "1_1") (pintype "passive"))
      (node (ref "C26") (pin "1") (pinfunction "1_1") (pintype "passive"))
      (node (ref "C27") (pin "1") (pinfunction "1_1") (pintype "passive"))
      (node (ref "C28") (pin "1") (pinfunction "1_1") (pintype "passive"))
      (node (ref "C4") (pin "2") (pinfunction "2_2") (pintype "passive"))
      (node (ref "C5") (pin "2") (pinfunction "2_2") (pintype "passive"))
      (node (ref "C9") (pin "1") (pinfunction "1_1") (pintype "passive"))
      (node (ref "DL3") (pin "C") (pinfunction "C_C") (pintype "passive"))
      (node (ref "GND1") (pin "X") (pinfunction "X_X") (pintype "passive"))
      (node (ref "GND2") (pin "X") (pinfunction "X_X") (pintype "passive"))
      (node (ref "J1") (pin "A1") (pinfunction "GND_A1") (pintype "passive"))
      (node (ref "J1") (pin "A12") (pinfunction "GND_A12") (pintype "passive"))
      (node (ref "J1") (pin "B1") (pinfunction "GND_B1") (pintype "passive"))
      (node (ref "J1") (pin "B12") (pinfunction "GND_B12") (pintype "passive"))
      (node (ref "JP1") (pin "14") (pinfunction "GND_14") (pintype "passive"))
      (node (ref "JP2") (pin "4") (pinfunction "GND_4") (pintype "passive"))
      (node (ref "M1") (pin "A1") (pinfunction "GND_A1") (pintype "passive"))
      (node (ref "M1") (pin "A9") (pinfunction "GND_A9") (pintype "passive"))
      (node (ref "M1") (pin "B2") (pinfunction "GND_B2") (pintype "passive"))
      (node (ref "M1") (pin "B8") (pinfunction "GND_B8") (pintype "passive"))
      (node (ref "M1") (pin "E4") (pinfunction "GND_E4") (pintype "passive"))
      (node (ref "M1") (pin "E5") (pinfunction "GND_E5") (pintype "passive"))
      (node (ref "M1") (pin "F4") (pinfunction "GND_F4") (pintype "passive"))
      (node (ref "M1") (pin "F5") (pinfunction "GND_F5") (pintype "passive"))
      (node (ref "M1") (pin "K2") (pinfunction "GND_K2") (pintype "passive"))
      (node (ref "M1") (pin "K3") (pinfunction "GND_K3") (pintype "passive"))
      (node (ref "M1") (pin "K5") (pinfunction "GND_K5") (pintype "passive"))
      (node (ref "M1") (pin "K7") (pinfunction "GND_K7") (pintype "passive"))
      (node (ref "M1") (pin "K8") (pinfunction "GND_K8") (pintype "passive"))
      (node (ref "M1") (pin "L1") (pinfunction "AGND_L1") (pintype "passive"))
      (node (ref "M1") (pin "L9") (pinfunction "AGND_L9") (pintype "passive"))
      (node (ref "M1") (pin "M1") (pinfunction "AGND_M1") (pintype "passive"))
      (node (ref "M1") (pin "M2") (pinfunction "AGND_M2") (pintype "passive"))
      (node (ref "M1") (pin "M8") (pinfunction "AGND_M8") (pintype "passive"))
      (node (ref "M1") (pin "M9") (pinfunction "AGND_M9") (pintype "passive"))
      (node (ref "PB1") (pin "1") (pinfunction "1_1") (pintype "passive"))
      (node (ref "Q1") (pin "S") (pinfunction "S_S") (pintype "passive"))
      (node (ref "R13") (pin "1") (pinfunction "1_1") (pintype "passive"))
      (node (ref "R21") (pin "1") (pinfunction "1_1") (pintype "passive"))
      (node (ref "R5") (pin "1") (pinfunction "1_1") (pintype "passive"))
      (node (ref "R6") (pin "1") (pinfunction "1_1") (pintype "passive"))
      (node (ref "R7") (pin "1") (pinfunction "1_1") (pintype "passive"))
      (node (ref "U2") (pin "1") (pinfunction "GND_1") (pintype "passive"))
      (node (ref "U3") (pin "4") (pinfunction "GND_4") (pintype "passive"))
      (node (ref "U3") (pin "9") (pinfunction "PAD_9") (pintype "passive"))
    )
    (net (code "44") (name "Net-(C25-Pad2)") (class "Default")
      (node (ref "C25") (pin "2") (pinfunction "2_2") (pintype "passive"))
      (node (ref "C26") (pin "2") (pinfunction "2_2") (pintype "passive"))
      (node (ref "L3") (pin "2") (pinfunction "2_2") (pintype "passive"))
      (node (ref "R18") (pin "2") (pinfunction "2_2") (pintype "passive"))
      (node (ref "SJ1") (pin "1") (pinfunction "1_1") (pintype "passive"))
    )
    (net (code "45") (name "Net-(DL1-BLUE_C)") (class "Default")
      (node (ref "DL1") (pin "3") (pinfunction "BLUE_C_3") (pintype "passive"))
      (node (ref "R12") (pin "2") (pinfunction "2_2") (pintype "passive"))
    )
    (net (code "46") (name "Net-(DL1-GREEN_C)") (class "Default")
      (node (ref "DL1") (pin "4") (pinfunction "GREEN_C_4") (pintype "passive"))
      (node (ref "R11") (pin "2") (pinfunction "2_2") (pintype "passive"))
    )
    (net (code "47") (name "Net-(DL1-RED_C)") (class "Default")
      (node (ref "DL1") (pin "2") (pinfunction "RED_C_2") (pintype "passive"))
      (node (ref "R10") (pin "2") (pinfunction "2_2") (pintype "passive"))
    )
    (net (code "48") (name "Net-(DL2-PadA)") (class "Default")
      (node (ref "DL2") (pin "A") (pinfunction "A_A") (pintype "passive"))
      (node (ref "R9") (pin "1") (pinfunction "1_1") (pintype "passive"))
    )
    (net (code "49") (name "Net-(DL2-PadC)") (class "Default")
      (node (ref "DL2") (pin "C") (pinfunction "C_C") (pintype "passive"))
      (node (ref "Q1") (pin "D") (pinfunction "D_D") (pintype "passive"))
    )
    (net (code "50") (name "Net-(DL3-PadA)") (class "Default")
      (node (ref "DL3") (pin "A") (pinfunction "A_A") (pintype "passive"))
      (node (ref "R8") (pin "1") (pinfunction "1_1") (pintype "passive"))
    )
    (net (code "51") (name "Net-(JP2-TX)") (class "Default")
      (node (ref "JP2") (pin "1") (pinfunction "TX_1") (pintype "passive"))
      (node (ref "R4") (pin "1") (pinfunction "1_1") (pintype "passive"))
    )
    (net (code "52") (name "Net-(M1-VDD_SPI)") (class "Default")
      (node (ref "C1") (pin "2") (pinfunction "2_2") (pintype "passive"))
      (node (ref "C12") (pin "2") (pinfunction "2_2") (pintype "passive"))
      (node (ref "L2") (pin "2") (pinfunction "2_2") (pintype "passive"))
      (node (ref "M1") (pin "A7") (pinfunction "VCCIO_A7") (pintype "power_in"))
      (node (ref "M1") (pin "B7") (pinfunction "VCCIO_B7") (pintype "power_in"))
      (node (ref "M1") (pin "J1") (pinfunction "VDD_SPI_J1") (pintype "power_in"))
    )
    (net (code "53") (name "Net-(M1-XTAL32KN_U0CTS_ADC2CH5_GPIO16)") (class "Default")
      (node (ref "C5") (pin "1") (pinfunction "1_1") (pintype "passive"))
      (node (ref "M1") (pin "B6") (pinfunction "XTAL32KN_U0CTS_ADC2CH5_GPIO16_B6") (pintype "passive"))
      (node (ref "Y1") (pin "1") (pinfunction "1_1") (pintype "passive"))
    )
    (net (code "54") (name "Net-(M1-XTAL32KP_U0RTS_ADC2CH4_GPIO15)") (class "Default")
      (node (ref "C4") (pin "1") (pinfunction "1_1") (pintype "passive"))
      (node (ref "M1") (pin "C6") (pinfunction "XTAL32KP_U0RTS_ADC2CH4_GPIO15_C6") (pintype "passive"))
      (node (ref "Y1") (pin "2") (pinfunction "2_2") (pintype "passive"))
    )
    (net (code "55") (name "Net-(U2-BST)") (class "Default")
      (node (ref "C20") (pin "2") (pinfunction "2_2") (pintype "passive"))
      (node (ref "U2") (pin "7") (pinfunction "BST_7") (pintype "passive"))
    )
    (net (code "56") (name "Net-(U2-FB)") (class "Default")
      (node (ref "C25") (pin "1") (pinfunction "1_1") (pintype "passive"))
      (node (ref "R18") (pin "1") (pinfunction "1_1") (pintype "passive"))
      (node (ref "R21") (pin "2") (pinfunction "2_2") (pintype "passive"))
      (node (ref "U2") (pin "5") (pinfunction "FB_5") (pintype "passive"))
    )
    (net (code "57") (name "Net-(U2-SW)") (class "Default")
      (node (ref "C20") (pin "1") (pinfunction "1_1") (pintype "passive"))
      (node (ref "L3") (pin "1") (pinfunction "1_1") (pintype "passive"))
      (node (ref "U2") (pin "8") (pinfunction "SW_8") (pintype "passive"))
    )
    (net (code "58") (name "Net-(U2-VCC)") (class "Default")
      (node (ref "C28") (pin "2") (pinfunction "2_2") (pintype "passive"))
      (node (ref "U2") (pin "4") (pinfunction "VCC_4") (pintype "passive"))
    )
    (net (code "59") (name "Net-(U3-IO0(SI))") (class "Default")
      (node (ref "R16") (pin "2") (pinfunction "2_2") (pintype "passive"))
      (node (ref "U3") (pin "5") (pinfunction "IO0(SI)_5") (pintype "passive"))
    )
    (net (code "60") (name "Net-(U3-IO1(SO))") (class "Default")
      (node (ref "R17") (pin "2") (pinfunction "2_2") (pintype "passive"))
      (node (ref "U3") (pin "2") (pinfunction "IO1(SO)_2") (pintype "passive"))
    )
    (net (code "61") (name "Net-(U3-IO2~{(WP}))") (class "Default")
      (node (ref "R19") (pin "2") (pinfunction "2_2") (pintype "passive"))
      (node (ref "U3") (pin "3") (pinfunction "IO2~{(WP})_3") (pintype "passive"))
    )
    (net (code "62") (name "Net-(U3-IO3~{(HOLD}))") (class "Default")
      (node (ref "R20") (pin "2") (pinfunction "2_2") (pintype "passive"))
      (node (ref "U3") (pin "7") (pinfunction "IO3~{(HOLD})_7") (pintype "passive"))
    )
    (net (code "63") (name "Net-(U3-SCK)") (class "Default")
      (node (ref "R14") (pin "2") (pinfunction "2_2") (pintype "passive"))
      (node (ref "U3") (pin "6") (pinfunction "SCK_6") (pintype "passive"))
    )
    (net (code "64") (name "Net-(U3-~{CS})") (class "Default")
      (node (ref "R15") (pin "2") (pinfunction "2_2") (pintype "passive"))
      (node (ref "U3") (pin "1") (pinfunction "~{CS}_1") (pintype "passive"))
    )
    (net (code "65") (name "VIN") (class "Default")
      (node (ref "C22") (pin "1") (pinfunction "1_1") (pintype "passive"))
      (node (ref "C23") (pin "2") (pinfunction "2_2") (pintype "passive"))
      (node (ref "C24") (pin "2") (pinfunction "2_2") (pintype "passive"))
      (node (ref "D2") (pin "C") (pinfunction "C_C") (pintype "passive"))
      (node (ref "JP1") (pin "15") (pinfunction "VIN_15") (pintype "passive"))
      (node (ref "U2") (pin "2") (pinfunction "IN_2") (pintype "passive"))
      (node (ref "U2") (pin "3") (pinfunction "EN_3") (pintype "passive"))
    )
    (net (code "66") (name "VUSB") (class "Default")
      (node (ref "D1") (pin "4") (pinfunction "4_4") (pintype "passive"))
      (node (ref "D2") (pin "A") (pinfunction "A_A") (pintype "passive"))
      (node (ref "J1") (pin "A4") (pinfunction "VBUS_A4") (pintype "passive"))
      (node (ref "J1") (pin "A9") (pinfunction "VBUS_A9") (pintype "passive"))
      (node (ref "J1") (pin "B4") (pinfunction "VBUS_B4") (pintype "passive"))
      (node (ref "J1") (pin "B9") (pinfunction "VBUS_B9") (pintype "passive"))
      (node (ref "JP1") (pin "12") (pinfunction "VUSB_12") (pintype "passive"))
      (node (ref "TP_VUSB") (pin "X") (pinfunction "X_X") (pintype "passive"))
      (node (ref "VUSB") (pin "X") (pinfunction "X_X") (pintype "passive"))
    )
    (net (code "67") (name "unconnected-(Fiducial_1-Pad1)") (class "Default")
      (node (ref "Fiducial_1") (pin "1") (pinfunction "1_1") (pintype "passive+no_connect"))
    )
    (net (code "68") (name "unconnected-(J1-PadFIXING)") (class "Default")
      (node (ref "J1") (pin "FIXING") (pinfunction "FIXING_FIXING") (pintype "passive+no_connect"))
    )
    (net (code "69") (name "unconnected-(J1-PadSHIELD2)") (class "Default")
      (node (ref "J1") (pin "SHIELD2") (pinfunction "SHIELD2_SHIELD2") (pintype "passive+no_connect"))
    )
    (net (code "70") (name "unconnected-(J1-PadSHIELD3)") (class "Default")
      (node (ref "J1") (pin "SHIELD3") (pinfunction "SHIELD3_SHIELD3") (pintype "passive+no_connect"))
    )
    (net (code "71") (name "unconnected-(J1-PadSHIELD4)") (class "Default")
      (node (ref "J1") (pin "SHIELD4") (pinfunction "SHIELD4_SHIELD4") (pintype "passive+no_connect"))
    )
    (net (code "72") (name "unconnected-(J1-SBU1-PadA8)") (class "Default")
      (node (ref "J1") (pin "A8") (pinfunction "SBU1_A8") (pintype "passive+no_connect"))
    )
    (net (code "73") (name "unconnected-(J1-SBU2-PadB8)") (class "Default")
      (node (ref "J1") (pin "B8") (pinfunction "SBU2_B8") (pintype "passive+no_connect"))
    )
    (net (code "74") (name "unconnected-(M1-ANT-PadK9)") (class "Default")
      (node (ref "M1") (pin "K9") (pinfunction "ANT_K9") (pintype "passive+no_connect"))
    )
    (net (code "75") (name "unconnected-(M1-FSPICLK_GPIO36-PadB1)") (class "Default")
      (node (ref "M1") (pin "B1") (pinfunction "FSPICLK_GPIO36_B1") (pintype "passive+no_connect"))
    )
    (net (code "76") (name "unconnected-(M1-FSPICS0_GPIO34-PadB3)") (class "Default")
      (node (ref "M1") (pin "B3") (pinfunction "FSPICS0_GPIO34_B3") (pintype "passive+no_connect"))
    )
    (net (code "77") (name "unconnected-(M1-FSPID_GPIO35-PadC2)") (class "Default")
      (node (ref "M1") (pin "C2") (pinfunction "FSPID_GPIO35_C2") (pintype "passive+no_connect"))
    )
    (net (code "78") (name "unconnected-(M1-FSPIHD_GPIO33-PadD3)") (class "Default")
      (node (ref "M1") (pin "D3") (pinfunction "FSPIHD_GPIO33_D3") (pintype "passive+no_connect"))
    )
    (net (code "79") (name "unconnected-(M1-FSPIQ_GPIO37-PadC1)") (class "Default")
      (node (ref "M1") (pin "C1") (pinfunction "FSPIQ_GPIO37_C1") (pintype "passive+no_connect"))
    )
    (net (code "80") (name "unconnected-(M1-NC-PadA4)") (class "Default")
      (node (ref "M1") (pin "A4") (pinfunction "NC_A4") (pintype "passive+no_connect"))
    )
    (net (code "81") (name "unconnected-(M1-NC-PadB5)") (class "Default")
      (node (ref "M1") (pin "B5") (pinfunction "NC_B5") (pintype "passive+no_connect"))
    )
    (net (code "82") (name "unconnected-(M1-NC-PadB9)") (class "Default")
      (node (ref "M1") (pin "B9") (pinfunction "NC_B9") (pintype "passive+no_connect"))
    )
    (net (code "83") (name "unconnected-(M1-NC-PadC5)") (class "Default")
      (node (ref "M1") (pin "C5") (pinfunction "NC_C5") (pintype "passive+no_connect"))
    )
    (net (code "84") (name "unconnected-(M1-NC-PadD7)") (class "Default")
      (node (ref "M1") (pin "D7") (pinfunction "NC_D7") (pintype "passive+no_connect"))
    )
    (net (code "85") (name "unconnected-(M1-NC-PadG4)") (class "Default")
      (node (ref "M1") (pin "G4") (pinfunction "NC_G4") (pintype "passive+no_connect"))
    )
    (net (code "86") (name "unconnected-(M1-NC-PadG5)") (class "Default")
      (node (ref "M1") (pin "G5") (pinfunction "NC_G5") (pintype "passive+no_connect"))
    )
    (net (code "87") (name "unconnected-(M1-NC-PadG7)") (class "Default")
      (node (ref "M1") (pin "G7") (pinfunction "NC_G7") (pintype "passive+no_connect"))
    )
    (net (code "88") (name "unconnected-(M1-NC-PadJ4)") (class "Default")
      (node (ref "M1") (pin "J4") (pinfunction "NC_J4") (pintype "passive+no_connect"))
    )
    (net (code "89") (name "unconnected-(M1-NC-PadJ5)") (class "Default")
      (node (ref "M1") (pin "J5") (pinfunction "NC_J5") (pintype "passive+no_connect"))
    )
    (net (code "90") (name "unconnected-(M1-NC-PadJ7)") (class "Default")
      (node (ref "M1") (pin "J7") (pinfunction "NC_J7") (pintype "passive+no_connect"))
    )
    (net (code "91") (name "unconnected-(M1-NC-PadK1)") (class "Default")
      (node (ref "M1") (pin "K1") (pinfunction "NC_K1") (pintype "passive+no_connect"))
    )
    (net (code "92") (name "unconnected-(M1-SPICS1_GPIO26-PadE1)") (class "Default")
      (node (ref "M1") (pin "E1") (pinfunction "SPICS1_GPIO26_E1") (pintype "passive+no_connect"))
    )
    (net (code "93") (name "unconnected-(NC1-PadX)") (class "Default")
      (node (ref "NC1") (pin "X") (pinfunction "X_X") (pintype "passive+no_connect"))
    )
    (net (code "94") (name "unconnected-(U2-PG-Pad6)") (class "Default")
      (node (ref "U2") (pin "6") (pinfunction "PG_6") (pintype "passive+no_connect"))
    )
  )
)
